# secondary_18.net
KiCad netlist of a schematic drawn in EAGLE
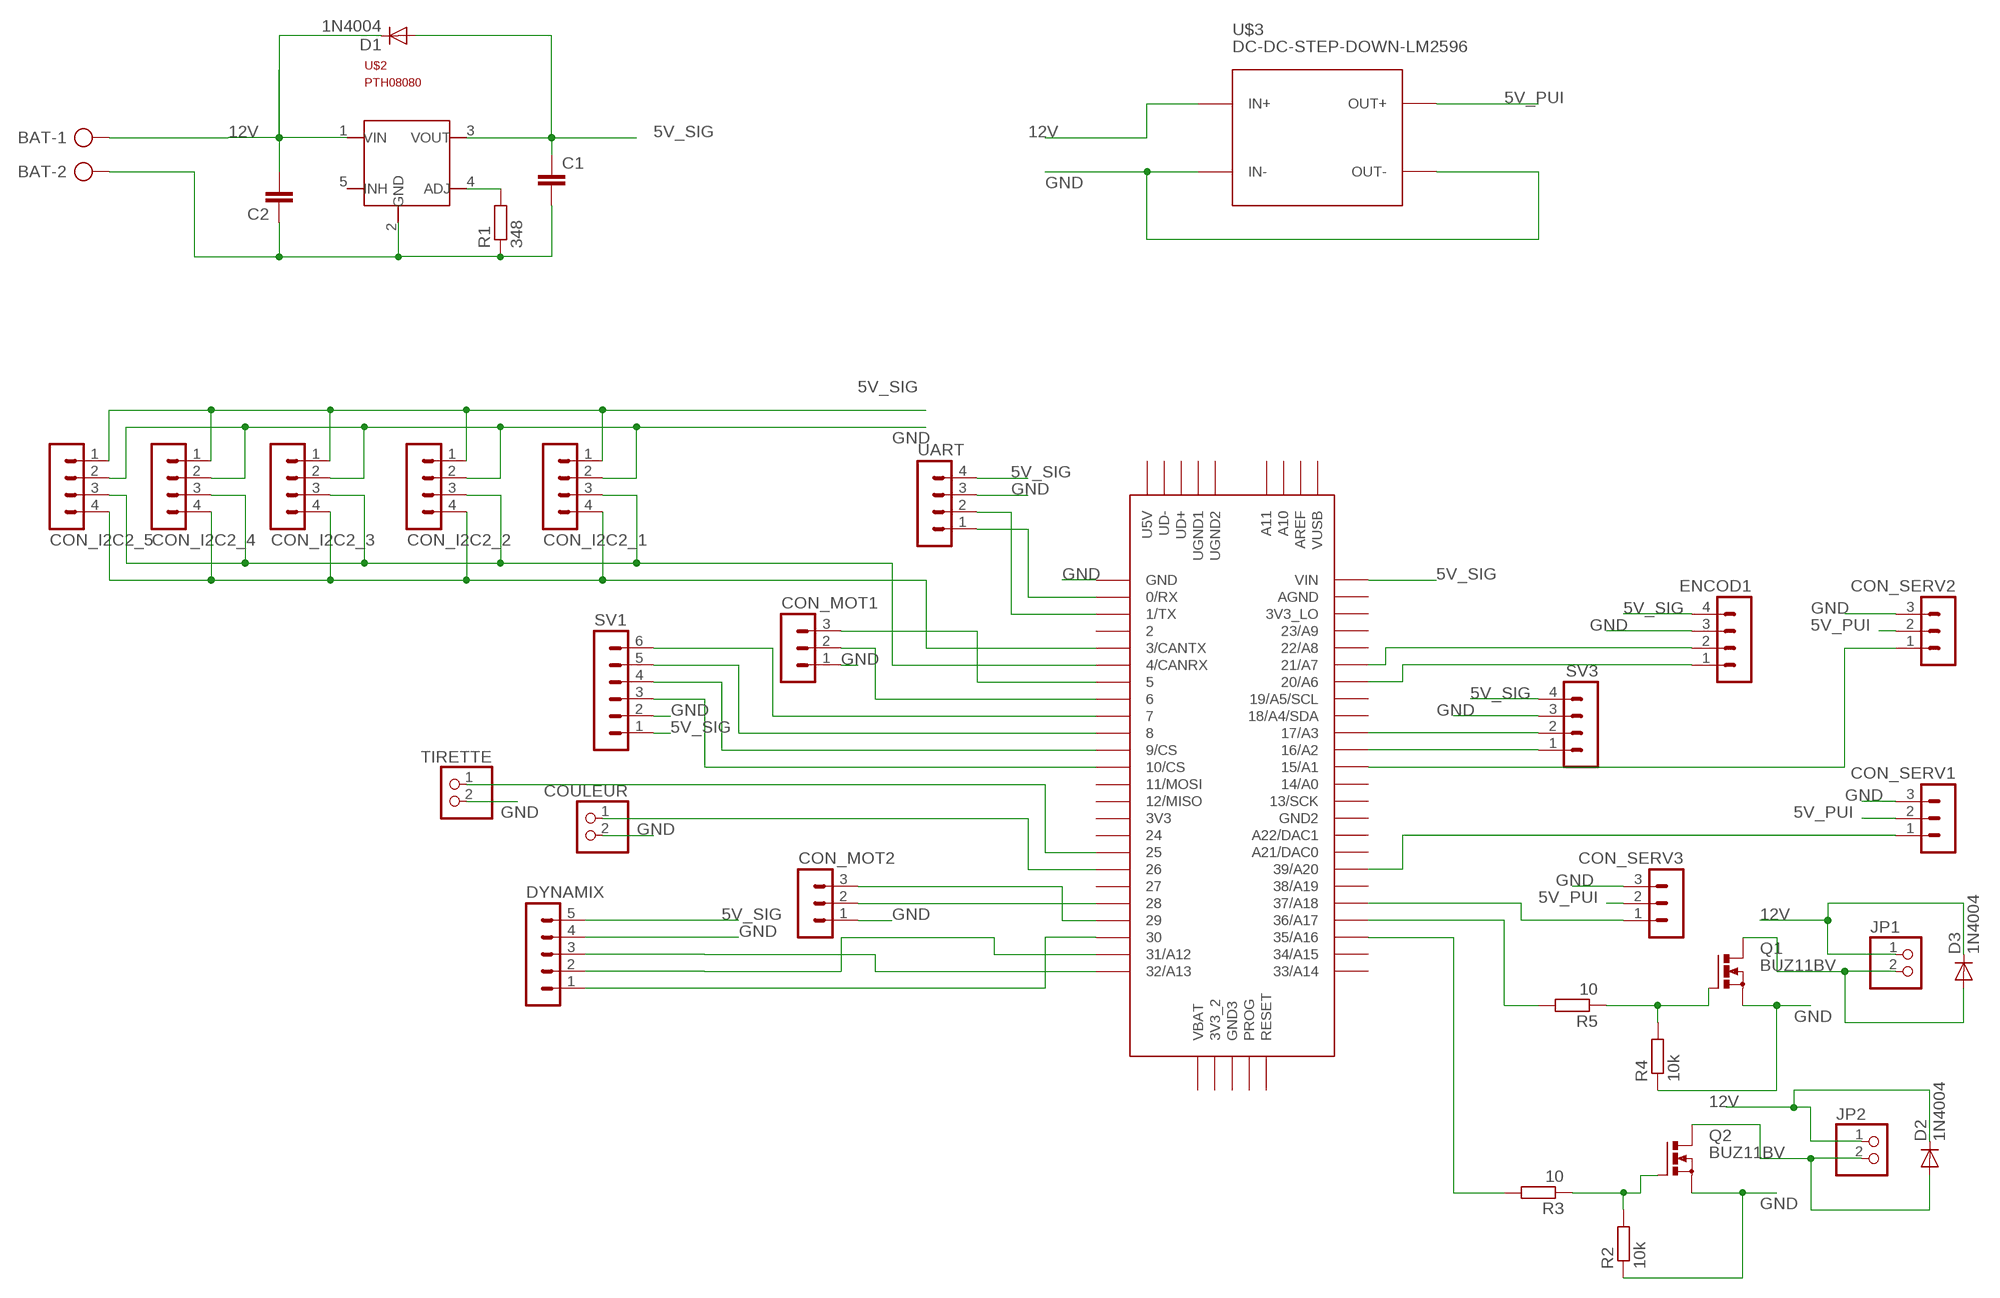
[diagram p0: schematic, sheet 1]

(export (version "E")
  (design (tool "Eeschema 10.0.6"))
  (components
    (comp (ref "BAT")
      (value "AK300/2")
      (footprint "eagle-import:AK300_2")
      (libsource (lib "eagle-import") (part "AK300/2"))
    )
    (comp (ref "C1")
      (value "C-EU025-060X050")
      (footprint "eagle-import:C025-060X050")
      (libsource (lib "eagle-import") (part "C-EU025-060X050"))
    )
    (comp (ref "C2")
      (value "C-EU025-060X050")
      (footprint "eagle-import:C025-060X050")
      (libsource (lib "eagle-import") (part "C-EU025-060X050"))
    )
    (comp (ref "CON_I2C2_1")
      (value "MA04-1")
      (footprint "eagle-import:MA04-1")
      (libsource (lib "eagle-import") (part "MA04-1"))
    )
    (comp (ref "CON_I2C2_2")
      (value "MA04-1")
      (footprint "eagle-import:MA04-1")
      (libsource (lib "eagle-import") (part "MA04-1"))
    )
    (comp (ref "CON_I2C2_3")
      (value "MA04-1")
      (footprint "eagle-import:MA04-1")
      (libsource (lib "eagle-import") (part "MA04-1"))
    )
    (comp (ref "CON_I2C2_4")
      (value "MA04-1")
      (footprint "eagle-import:MA04-1")
      (libsource (lib "eagle-import") (part "MA04-1"))
    )
    (comp (ref "CON_I2C2_5")
      (value "MA04-1")
      (footprint "eagle-import:MA04-1")
      (libsource (lib "eagle-import") (part "MA04-1"))
    )
    (comp (ref "CON_MOT1")
      (value "MA03-1")
      (footprint "eagle-import:MA03-1")
      (libsource (lib "eagle-import") (part "MA03-1"))
    )
    (comp (ref "CON_MOT2")
      (value "MA03-1")
      (footprint "eagle-import:MA03-1")
      (libsource (lib "eagle-import") (part "MA03-1"))
    )
    (comp (ref "CON_SERV1")
      (value "MA03-1")
      (footprint "eagle-import:MA03-1")
      (libsource (lib "eagle-import") (part "MA03-1"))
    )
    (comp (ref "CON_SERV2")
      (value "MA03-1")
      (footprint "eagle-import:MA03-1")
      (libsource (lib "eagle-import") (part "MA03-1"))
    )
    (comp (ref "CON_SERV3")
      (value "MA03-1")
      (footprint "eagle-import:MA03-1")
      (libsource (lib "eagle-import") (part "MA03-1"))
    )
    (comp (ref "COULEUR")
      (value "PINHD-1X2")
      (footprint "eagle-import:1X02")
      (libsource (lib "eagle-import") (part "PINHD-1X2"))
    )
    (comp (ref "D1")
      (value "1N4004")
      (footprint "eagle-import:DO41-10")
      (libsource (lib "eagle-import") (part "1N4004"))
    )
    (comp (ref "D2")
      (value "1N4004")
      (footprint "eagle-import:DO41-10")
      (libsource (lib "eagle-import") (part "1N4004"))
    )
    (comp (ref "D3")
      (value "1N4004")
      (footprint "eagle-import:DO41-10")
      (libsource (lib "eagle-import") (part "1N4004"))
    )
    (comp (ref "DYNAMIX")
      (value "MA05-1")
      (footprint "eagle-import:MA05-1")
      (libsource (lib "eagle-import") (part "MA05-1"))
    )
    (comp (ref "ENCOD1")
      (value "MA04-1")
      (footprint "eagle-import:MA04-1")
      (libsource (lib "eagle-import") (part "MA04-1"))
    )
    (comp (ref "JP1")
      (value "PINHD-1X2")
      (footprint "eagle-import:1X02")
      (libsource (lib "eagle-import") (part "PINHD-1X2"))
    )
    (comp (ref "JP2")
      (value "PINHD-1X2")
      (footprint "eagle-import:1X02")
      (libsource (lib "eagle-import") (part "PINHD-1X2"))
    )
    (comp (ref "Q1")
      (value "BUZ11BV")
      (footprint "eagle-import:TO220BV")
      (libsource (lib "eagle-import") (part "BUZ11BV"))
    )
    (comp (ref "Q2")
      (value "BUZ11BV")
      (footprint "eagle-import:TO220BV")
      (libsource (lib "eagle-import") (part "BUZ11BV"))
    )
    (comp (ref "R1")
      (value "348")
      (footprint "eagle-import:0204_7")
      (libsource (lib "eagle-import") (part "R-EU_0204/7"))
    )
    (comp (ref "R2")
      (value "10k")
      (footprint "eagle-import:0204_7")
      (libsource (lib "eagle-import") (part "R-EU_0204/7"))
    )
    (comp (ref "R3")
      (value "10")
      (footprint "eagle-import:0204_7")
      (libsource (lib "eagle-import") (part "R-EU_0204/7"))
    )
    (comp (ref "R4")
      (value "10k")
      (footprint "eagle-import:0204_7")
      (libsource (lib "eagle-import") (part "R-EU_0204/7"))
    )
    (comp (ref "R5")
      (value "10")
      (footprint "eagle-import:0204_7")
      (libsource (lib "eagle-import") (part "R-EU_0204/7"))
    )
    (comp (ref "SV1")
      (value "MA06-1")
      (footprint "eagle-import:MA06-1")
      (libsource (lib "eagle-import") (part "MA06-1"))
    )
    (comp (ref "SV3")
      (value "MA04-1")
      (footprint "eagle-import:MA04-1")
      (libsource (lib "eagle-import") (part "MA04-1"))
    )
    (comp (ref "TIRETTE")
      (value "PINHD-1X2")
      (footprint "eagle-import:1X02")
      (libsource (lib "eagle-import") (part "PINHD-1X2"))
    )
    (comp (ref "U$1")
      (value "TEENSY_3.5/3.6")
      (footprint "eagle-import:TEENSY_3.5_3.6")
      (libsource (lib "eagle-import") (part "TEENSY_3.5/3.6"))
    )
    (comp (ref "U$2")
      (value "PTH08080")
      (footprint "eagle-import:PTH08080EUF")
      (libsource (lib "eagle-import") (part "PTH08080"))
    )
    (comp (ref "U$3")
      (value "DC-DC-STEP-DOWN-LM2596")
      (footprint "eagle-import:DC-DC-STEP-DOWN-LM2596")
      (libsource (lib "eagle-import") (part "DC-DC-STEP-DOWN-LM2596"))
    )
    (comp (ref "UART")
      (value "MA04-1")
      (footprint "eagle-import:MA04-1")
      (libsource (lib "eagle-import") (part "MA04-1"))
    )
  )
  (nets
    (net (code "1") (name "/5V_PUI") (class "Default")
      (node (ref "CON_SERV1") (pin "2") (pinfunction "2_2") (pintype "passive"))
      (node (ref "CON_SERV2") (pin "2") (pinfunction "2_2") (pintype "passive"))
      (node (ref "CON_SERV3") (pin "2") (pinfunction "2_2") (pintype "passive"))
      (node (ref "U$3") (pin "OUT+") (pinfunction "OUT+_OUT+") (pintype "bidirectional"))
    )
    (net (code "2") (name "/5V_SIG") (class "Default")
      (node (ref "C1") (pin "1") (pinfunction "1_1") (pintype "passive"))
      (node (ref "CON_I2C2_1") (pin "1") (pinfunction "1_1") (pintype "passive"))
      (node (ref "CON_I2C2_2") (pin "1") (pinfunction "1_1") (pintype "passive"))
      (node (ref "CON_I2C2_3") (pin "1") (pinfunction "1_1") (pintype "passive"))
      (node (ref "CON_I2C2_4") (pin "1") (pinfunction "1_1") (pintype "passive"))
      (node (ref "CON_I2C2_5") (pin "1") (pinfunction "1_1") (pintype "passive"))
      (node (ref "D1") (pin "A") (pinfunction "A_A") (pintype "passive"))
      (node (ref "DYNAMIX") (pin "5") (pinfunction "5_5") (pintype "passive"))
      (node (ref "ENCOD1") (pin "4") (pinfunction "4_4") (pintype "passive"))
      (node (ref "SV1") (pin "1") (pinfunction "1_1") (pintype "passive"))
      (node (ref "SV3") (pin "4") (pinfunction "4_4") (pintype "passive"))
      (node (ref "U$1") (pin "VIN") (pinfunction "VIN_VIN") (pintype "bidirectional"))
      (node (ref "U$2") (pin "3") (pinfunction "VOUT_3") (pintype "power_in"))
      (node (ref "UART") (pin "4") (pinfunction "4_4") (pintype "passive"))
    )
    (net (code "3") (name "/12V") (class "Default")
      (node (ref "BAT") (pin "1") (pinfunction "KL_1") (pintype "passive"))
      (node (ref "C2") (pin "2") (pinfunction "2_2") (pintype "passive"))
      (node (ref "D1") (pin "C") (pinfunction "C_C") (pintype "passive"))
      (node (ref "D2") (pin "C") (pinfunction "C_C") (pintype "passive"))
      (node (ref "D3") (pin "C") (pinfunction "C_C") (pintype "passive"))
      (node (ref "JP1") (pin "1") (pinfunction "1_1") (pintype "passive"))
      (node (ref "JP2") (pin "1") (pinfunction "1_1") (pintype "passive"))
      (node (ref "U$2") (pin "1") (pinfunction "VIN_1") (pintype "power_in"))
      (node (ref "U$3") (pin "IN+") (pinfunction "IN+_IN+") (pintype "bidirectional"))
    )
    (net (code "4") (name "/GND") (class "Default")
      (node (ref "BAT") (pin "2") (pinfunction "KL_2") (pintype "passive"))
      (node (ref "C1") (pin "2") (pinfunction "2_2") (pintype "passive"))
      (node (ref "C2") (pin "1") (pinfunction "1_1") (pintype "passive"))
      (node (ref "CON_I2C2_1") (pin "2") (pinfunction "2_2") (pintype "passive"))
      (node (ref "CON_I2C2_2") (pin "2") (pinfunction "2_2") (pintype "passive"))
      (node (ref "CON_I2C2_3") (pin "2") (pinfunction "2_2") (pintype "passive"))
      (node (ref "CON_I2C2_4") (pin "2") (pinfunction "2_2") (pintype "passive"))
      (node (ref "CON_I2C2_5") (pin "2") (pinfunction "2_2") (pintype "passive"))
      (node (ref "CON_MOT1") (pin "1") (pinfunction "1_1") (pintype "passive"))
      (node (ref "CON_MOT2") (pin "1") (pinfunction "1_1") (pintype "passive"))
      (node (ref "CON_SERV1") (pin "3") (pinfunction "3_3") (pintype "passive"))
      (node (ref "CON_SERV2") (pin "3") (pinfunction "3_3") (pintype "passive"))
      (node (ref "CON_SERV3") (pin "3") (pinfunction "3_3") (pintype "passive"))
      (node (ref "COULEUR") (pin "2") (pinfunction "2_2") (pintype "passive"))
      (node (ref "DYNAMIX") (pin "4") (pinfunction "4_4") (pintype "passive"))
      (node (ref "ENCOD1") (pin "3") (pinfunction "3_3") (pintype "passive"))
      (node (ref "Q1") (pin "S") (pinfunction "S_S") (pintype "passive"))
      (node (ref "Q2") (pin "S") (pinfunction "S_S") (pintype "passive"))
      (node (ref "R1") (pin "1") (pinfunction "1_1") (pintype "passive"))
      (node (ref "R2") (pin "1") (pinfunction "1_1") (pintype "passive"))
      (node (ref "R4") (pin "1") (pinfunction "1_1") (pintype "passive"))
      (node (ref "SV1") (pin "2") (pinfunction "2_2") (pintype "passive"))
      (node (ref "SV3") (pin "3") (pinfunction "3_3") (pintype "passive"))
      (node (ref "TIRETTE") (pin "2") (pinfunction "2_2") (pintype "passive"))
      (node (ref "U$1") (pin "GND") (pinfunction "GND_GND") (pintype "bidirectional"))
      (node (ref "U$2") (pin "2") (pinfunction "GND_2") (pintype "power_in"))
      (node (ref "U$3") (pin "IN-") (pinfunction "IN-_IN-") (pintype "bidirectional"))
      (node (ref "U$3") (pin "OUT-") (pinfunction "OUT-_OUT-") (pintype "bidirectional"))
      (node (ref "UART") (pin "3") (pinfunction "3_3") (pintype "passive"))
    )
    (net (code "5") (name "Net-(CON_I2C2_1-Pad3)") (class "Default")
      (node (ref "CON_I2C2_1") (pin "3") (pinfunction "3_3") (pintype "passive"))
      (node (ref "CON_I2C2_2") (pin "3") (pinfunction "3_3") (pintype "passive"))
      (node (ref "CON_I2C2_3") (pin "3") (pinfunction "3_3") (pintype "passive"))
      (node (ref "CON_I2C2_4") (pin "3") (pinfunction "3_3") (pintype "passive"))
      (node (ref "CON_I2C2_5") (pin "3") (pinfunction "3_3") (pintype "passive"))
      (node (ref "U$1") (pin "4/CANRX") (pinfunction "4/CANRX_4/CANRX") (pintype "bidirectional"))
    )
    (net (code "6") (name "Net-(CON_I2C2_1-Pad4)") (class "Default")
      (node (ref "CON_I2C2_1") (pin "4") (pinfunction "4_4") (pintype "passive"))
      (node (ref "CON_I2C2_2") (pin "4") (pinfunction "4_4") (pintype "passive"))
      (node (ref "CON_I2C2_3") (pin "4") (pinfunction "4_4") (pintype "passive"))
      (node (ref "CON_I2C2_4") (pin "4") (pinfunction "4_4") (pintype "passive"))
      (node (ref "CON_I2C2_5") (pin "4") (pinfunction "4_4") (pintype "passive"))
      (node (ref "U$1") (pin "3/CANTX") (pinfunction "3/CANTX_3/CANTX") (pintype "bidirectional"))
    )
    (net (code "7") (name "Net-(CON_MOT1-Pad2)") (class "Default")
      (node (ref "CON_MOT1") (pin "2") (pinfunction "2_2") (pintype "passive"))
      (node (ref "U$1") (pin "6") (pinfunction "6_6") (pintype "bidirectional"))
    )
    (net (code "8") (name "Net-(CON_MOT1-Pad3)") (class "Default")
      (node (ref "CON_MOT1") (pin "3") (pinfunction "3_3") (pintype "passive"))
      (node (ref "U$1") (pin "5") (pinfunction "5_5") (pintype "bidirectional"))
    )
    (net (code "9") (name "Net-(CON_MOT2-Pad2)") (class "Default")
      (node (ref "CON_MOT2") (pin "2") (pinfunction "2_2") (pintype "passive"))
      (node (ref "U$1") (pin "28") (pinfunction "28_28") (pintype "bidirectional"))
    )
    (net (code "10") (name "Net-(CON_MOT2-Pad3)") (class "Default")
      (node (ref "CON_MOT2") (pin "3") (pinfunction "3_3") (pintype "passive"))
      (node (ref "U$1") (pin "29") (pinfunction "29_29") (pintype "bidirectional"))
    )
    (net (code "11") (name "Net-(CON_SERV1-Pad1)") (class "Default")
      (node (ref "CON_SERV1") (pin "1") (pinfunction "1_1") (pintype "passive"))
      (node (ref "U$1") (pin "39/A20") (pinfunction "39/A20_39/A20") (pintype "bidirectional"))
    )
    (net (code "12") (name "Net-(CON_SERV2-Pad1)") (class "Default")
      (node (ref "CON_SERV2") (pin "1") (pinfunction "1_1") (pintype "passive"))
      (node (ref "U$1") (pin "15/A1") (pinfunction "15/A1_15/A1") (pintype "bidirectional"))
    )
    (net (code "13") (name "Net-(CON_SERV3-Pad1)") (class "Default")
      (node (ref "CON_SERV3") (pin "1") (pinfunction "1_1") (pintype "passive"))
      (node (ref "U$1") (pin "37/A18") (pinfunction "37/A18_37/A18") (pintype "bidirectional"))
    )
    (net (code "14") (name "Net-(COULEUR-Pad1)") (class "Default")
      (node (ref "COULEUR") (pin "1") (pinfunction "1_1") (pintype "passive"))
      (node (ref "U$1") (pin "26") (pinfunction "26_26") (pintype "bidirectional"))
    )
    (net (code "15") (name "Net-(D2-PadA)") (class "Default")
      (node (ref "D2") (pin "A") (pinfunction "A_A") (pintype "passive"))
      (node (ref "JP2") (pin "2") (pinfunction "2_2") (pintype "passive"))
      (node (ref "Q2") (pin "D") (pinfunction "D_D") (pintype "passive"))
    )
    (net (code "16") (name "Net-(D3-PadA)") (class "Default")
      (node (ref "D3") (pin "A") (pinfunction "A_A") (pintype "passive"))
      (node (ref "JP1") (pin "2") (pinfunction "2_2") (pintype "passive"))
      (node (ref "Q1") (pin "D") (pinfunction "D_D") (pintype "passive"))
    )
    (net (code "17") (name "Net-(DYNAMIX-Pad1)") (class "Default")
      (node (ref "DYNAMIX") (pin "1") (pinfunction "1_1") (pintype "passive"))
      (node (ref "U$1") (pin "30") (pinfunction "30_30") (pintype "bidirectional"))
    )
    (net (code "18") (name "Net-(DYNAMIX-Pad2)") (class "Default")
      (node (ref "DYNAMIX") (pin "2") (pinfunction "2_2") (pintype "passive"))
      (node (ref "U$1") (pin "31/A12") (pinfunction "31/A12_31/A12") (pintype "bidirectional"))
    )
    (net (code "19") (name "Net-(DYNAMIX-Pad3)") (class "Default")
      (node (ref "DYNAMIX") (pin "3") (pinfunction "3_3") (pintype "passive"))
      (node (ref "U$1") (pin "32/A13") (pinfunction "32/A13_32/A13") (pintype "bidirectional"))
    )
    (net (code "20") (name "Net-(ENCOD1-Pad1)") (class "Default")
      (node (ref "ENCOD1") (pin "1") (pinfunction "1_1") (pintype "passive"))
      (node (ref "U$1") (pin "20/A6") (pinfunction "20/A6_20/A6") (pintype "bidirectional"))
    )
    (net (code "21") (name "Net-(ENCOD1-Pad2)") (class "Default")
      (node (ref "ENCOD1") (pin "2") (pinfunction "2_2") (pintype "passive"))
      (node (ref "U$1") (pin "21/A7") (pinfunction "21/A7_21/A7") (pintype "bidirectional"))
    )
    (net (code "22") (name "Net-(Q1-PadG)") (class "Default")
      (node (ref "Q1") (pin "G") (pinfunction "G_G") (pintype "passive"))
      (node (ref "R4") (pin "2") (pinfunction "2_2") (pintype "passive"))
      (node (ref "R5") (pin "1") (pinfunction "1_1") (pintype "passive"))
    )
    (net (code "23") (name "Net-(Q2-PadG)") (class "Default")
      (node (ref "Q2") (pin "G") (pinfunction "G_G") (pintype "passive"))
      (node (ref "R2") (pin "2") (pinfunction "2_2") (pintype "passive"))
      (node (ref "R3") (pin "1") (pinfunction "1_1") (pintype "passive"))
    )
    (net (code "24") (name "Net-(R3-Pad2)") (class "Default")
      (node (ref "R3") (pin "2") (pinfunction "2_2") (pintype "passive"))
      (node (ref "U$1") (pin "35/A16") (pinfunction "35/A16_35/A16") (pintype "bidirectional"))
    )
    (net (code "25") (name "Net-(R5-Pad2)") (class "Default")
      (node (ref "R5") (pin "2") (pinfunction "2_2") (pintype "passive"))
      (node (ref "U$1") (pin "36/A17") (pinfunction "36/A17_36/A17") (pintype "bidirectional"))
    )
    (net (code "26") (name "Net-(SV1-Pad3)") (class "Default")
      (node (ref "SV1") (pin "3") (pinfunction "3_3") (pintype "passive"))
      (node (ref "U$1") (pin "10/CS") (pinfunction "10/CS_10/CS") (pintype "bidirectional"))
    )
    (net (code "27") (name "Net-(SV1-Pad4)") (class "Default")
      (node (ref "SV1") (pin "4") (pinfunction "4_4") (pintype "passive"))
      (node (ref "U$1") (pin "9/CS") (pinfunction "9/CS_9/CS") (pintype "bidirectional"))
    )
    (net (code "28") (name "Net-(SV1-Pad5)") (class "Default")
      (node (ref "SV1") (pin "5") (pinfunction "5_5") (pintype "passive"))
      (node (ref "U$1") (pin "8") (pinfunction "8_8") (pintype "bidirectional"))
    )
    (net (code "29") (name "Net-(SV1-Pad6)") (class "Default")
      (node (ref "SV1") (pin "6") (pinfunction "6_6") (pintype "passive"))
      (node (ref "U$1") (pin "7") (pinfunction "7_7") (pintype "bidirectional"))
    )
    (net (code "30") (name "Net-(SV3-Pad1)") (class "Default")
      (node (ref "SV3") (pin "1") (pinfunction "1_1") (pintype "passive"))
      (node (ref "U$1") (pin "16/A2") (pinfunction "16/A2_16/A2") (pintype "bidirectional"))
    )
    (net (code "31") (name "Net-(SV3-Pad2)") (class "Default")
      (node (ref "SV3") (pin "2") (pinfunction "2_2") (pintype "passive"))
      (node (ref "U$1") (pin "17/A3") (pinfunction "17/A3_17/A3") (pintype "bidirectional"))
    )
    (net (code "32") (name "Net-(TIRETTE-Pad1)") (class "Default")
      (node (ref "TIRETTE") (pin "1") (pinfunction "1_1") (pintype "passive"))
      (node (ref "U$1") (pin "25") (pinfunction "25_25") (pintype "bidirectional"))
    )
    (net (code "33") (name "Net-(U$1-Pad0{slash}RX)") (class "Default")
      (node (ref "U$1") (pin "0/RX") (pinfunction "0/RX_0/RX") (pintype "bidirectional"))
      (node (ref "UART") (pin "1") (pinfunction "1_1") (pintype "passive"))
    )
    (net (code "34") (name "Net-(U$1-Pad1{slash}TX)") (class "Default")
      (node (ref "U$1") (pin "1/TX") (pinfunction "1/TX_1/TX") (pintype "bidirectional"))
      (node (ref "UART") (pin "2") (pinfunction "2_2") (pintype "passive"))
    )
    (net (code "35") (name "Net-(U$2-ADJ)") (class "Default")
      (node (ref "R1") (pin "2") (pinfunction "2_2") (pintype "passive"))
      (node (ref "U$2") (pin "4") (pinfunction "ADJ_4") (pintype "passive"))
    )
    (net (code "36") (name "unconnected-(U$1-A21{slash}DAC0-Pad21{slash}DAC0)") (class "Default")
      (node (ref "U$1") (pin "21/DAC0") (pinfunction "A21/DAC0_21/DAC0") (pintype "bidirectional"))
    )
    (net (code "37") (name "unconnected-(U$1-Pad2)") (class "Default")
      (node (ref "U$1") (pin "2") (pinfunction "2_2") (pintype "bidirectional"))
    )
    (net (code "38") (name "unconnected-(U$1-Pad3V3)") (class "Default")
      (node (ref "U$1") (pin "3V3") (pinfunction "3V3_3V3") (pintype "bidirectional"))
    )
    (net (code "39") (name "unconnected-(U$1-Pad3V3_2)") (class "Default")
      (node (ref "U$1") (pin "3V3_2") (pinfunction "3V3_2_3V3_2") (pintype "bidirectional"))
    )
    (net (code "40") (name "unconnected-(U$1-Pad3V3_LO)") (class "Default")
      (node (ref "U$1") (pin "3V3_LO") (pinfunction "3V3_LO_3V3_LO") (pintype "bidirectional"))
    )
    (net (code "41") (name "unconnected-(U$1-Pad11{slash}MOSI)") (class "Default")
      (node (ref "U$1") (pin "11/MOSI") (pinfunction "11/MOSI_11/MOSI") (pintype "bidirectional"))
    )
    (net (code "42") (name "unconnected-(U$1-Pad12{slash}MISO)") (class "Default")
      (node (ref "U$1") (pin "12/MISO") (pinfunction "12/MISO_12/MISO") (pintype "bidirectional"))
    )
    (net (code "43") (name "unconnected-(U$1-Pad13{slash}SCK)") (class "Default")
      (node (ref "U$1") (pin "13/SCK") (pinfunction "13/SCK_13/SCK") (pintype "bidirectional"))
    )
    (net (code "44") (name "unconnected-(U$1-Pad14{slash}A0)") (class "Default")
      (node (ref "U$1") (pin "14/A0") (pinfunction "14/A0_14/A0") (pintype "bidirectional"))
    )
    (net (code "45") (name "unconnected-(U$1-Pad18{slash}A4{slash}SDA)") (class "Default")
      (node (ref "U$1") (pin "18/A4/SDA") (pinfunction "18/A4/SDA_18/A4/SDA") (pintype "bidirectional"))
    )
    (net (code "46") (name "unconnected-(U$1-Pad19{slash}A5{slash}SCL)") (class "Default")
      (node (ref "U$1") (pin "19/A5/SCL") (pinfunction "19/A5/SCL_19/A5/SCL") (pintype "bidirectional"))
    )
    (net (code "47") (name "unconnected-(U$1-Pad22{slash}A8)") (class "Default")
      (node (ref "U$1") (pin "22/A8") (pinfunction "22/A8_22/A8") (pintype "bidirectional"))
    )
    (net (code "48") (name "unconnected-(U$1-Pad23{slash}A9)") (class "Default")
      (node (ref "U$1") (pin "23/A9") (pinfunction "23/A9_23/A9") (pintype "bidirectional"))
    )
    (net (code "49") (name "unconnected-(U$1-Pad24)") (class "Default")
      (node (ref "U$1") (pin "24") (pinfunction "24_24") (pintype "bidirectional"))
    )
    (net (code "50") (name "unconnected-(U$1-Pad27)") (class "Default")
      (node (ref "U$1") (pin "27") (pinfunction "27_27") (pintype "bidirectional"))
    )
    (net (code "51") (name "unconnected-(U$1-Pad33{slash}A14)") (class "Default")
      (node (ref "U$1") (pin "33/A14") (pinfunction "33/A14_33/A14") (pintype "bidirectional"))
    )
    (net (code "52") (name "unconnected-(U$1-Pad34{slash}A15)") (class "Default")
      (node (ref "U$1") (pin "34/A15") (pinfunction "34/A15_34/A15") (pintype "bidirectional"))
    )
    (net (code "53") (name "unconnected-(U$1-Pad38{slash}A19)") (class "Default")
      (node (ref "U$1") (pin "38/A19") (pinfunction "38/A19_38/A19") (pintype "bidirectional"))
    )
    (net (code "54") (name "unconnected-(U$1-PadA10)") (class "Default")
      (node (ref "U$1") (pin "A10") (pinfunction "A10_A10") (pintype "bidirectional"))
    )
    (net (code "55") (name "unconnected-(U$1-PadA11)") (class "Default")
      (node (ref "U$1") (pin "A11") (pinfunction "A11_A11") (pintype "bidirectional"))
    )
    (net (code "56") (name "unconnected-(U$1-PadA22{slash}DAC1)") (class "Default")
      (node (ref "U$1") (pin "A22/DAC1") (pinfunction "A22/DAC1_A22/DAC1") (pintype "bidirectional"))
    )
    (net (code "57") (name "unconnected-(U$1-PadAGND)") (class "Default")
      (node (ref "U$1") (pin "AGND") (pinfunction "AGND_AGND") (pintype "bidirectional"))
    )
    (net (code "58") (name "unconnected-(U$1-PadAREF)") (class "Default")
      (node (ref "U$1") (pin "AREF") (pinfunction "AREF_AREF") (pintype "bidirectional"))
    )
    (net (code "59") (name "unconnected-(U$1-PadGND2)") (class "Default")
      (node (ref "U$1") (pin "GND2") (pinfunction "GND2_GND2") (pintype "bidirectional"))
    )
    (net (code "60") (name "unconnected-(U$1-PadGND3)") (class "Default")
      (node (ref "U$1") (pin "GND3") (pinfunction "GND3_GND3") (pintype "bidirectional"))
    )
    (net (code "61") (name "unconnected-(U$1-PadPROG)") (class "Default")
      (node (ref "U$1") (pin "PROG") (pinfunction "PROG_PROG") (pintype "bidirectional"))
    )
    (net (code "62") (name "unconnected-(U$1-PadRESET)") (class "Default")
      (node (ref "U$1") (pin "RESET") (pinfunction "RESET_RESET") (pintype "bidirectional"))
    )
    (net (code "63") (name "unconnected-(U$1-PadU5V)") (class "Default")
      (node (ref "U$1") (pin "U5V") (pinfunction "U5V_U5V") (pintype "bidirectional"))
    )
    (net (code "64") (name "unconnected-(U$1-PadUD+)") (class "Default")
      (node (ref "U$1") (pin "UD+") (pinfunction "UD+_UD+") (pintype "bidirectional"))
    )
    (net (code "65") (name "unconnected-(U$1-PadUD-)") (class "Default")
      (node (ref "U$1") (pin "UD-") (pinfunction "UD-_UD-") (pintype "bidirectional"))
    )
    (net (code "66") (name "unconnected-(U$1-PadUGND1)") (class "Default")
      (node (ref "U$1") (pin "UGND1") (pinfunction "UGND1_UGND1") (pintype "bidirectional"))
    )
    (net (code "67") (name "unconnected-(U$1-PadUGND2)") (class "Default")
      (node (ref "U$1") (pin "UGND2") (pinfunction "UGND2_UGND2") (pintype "bidirectional"))
    )
    (net (code "68") (name "unconnected-(U$1-PadVBAT)") (class "Default")
      (node (ref "U$1") (pin "VBAT") (pinfunction "VBAT_VBAT") (pintype "bidirectional"))
    )
    (net (code "69") (name "unconnected-(U$1-PadVUSB)") (class "Default")
      (node (ref "U$1") (pin "VUSB") (pinfunction "VUSB_VUSB") (pintype "bidirectional"))
    )
    (net (code "70") (name "unconnected-(U$2-INH-Pad5)") (class "Default")
      (node (ref "U$2") (pin "5") (pinfunction "INH_5") (pintype "bidirectional"))
    )
  )
)
